# 1-Schematic_Line_Following.net
KiCad netlist of a schematic drawn in EasyEDA
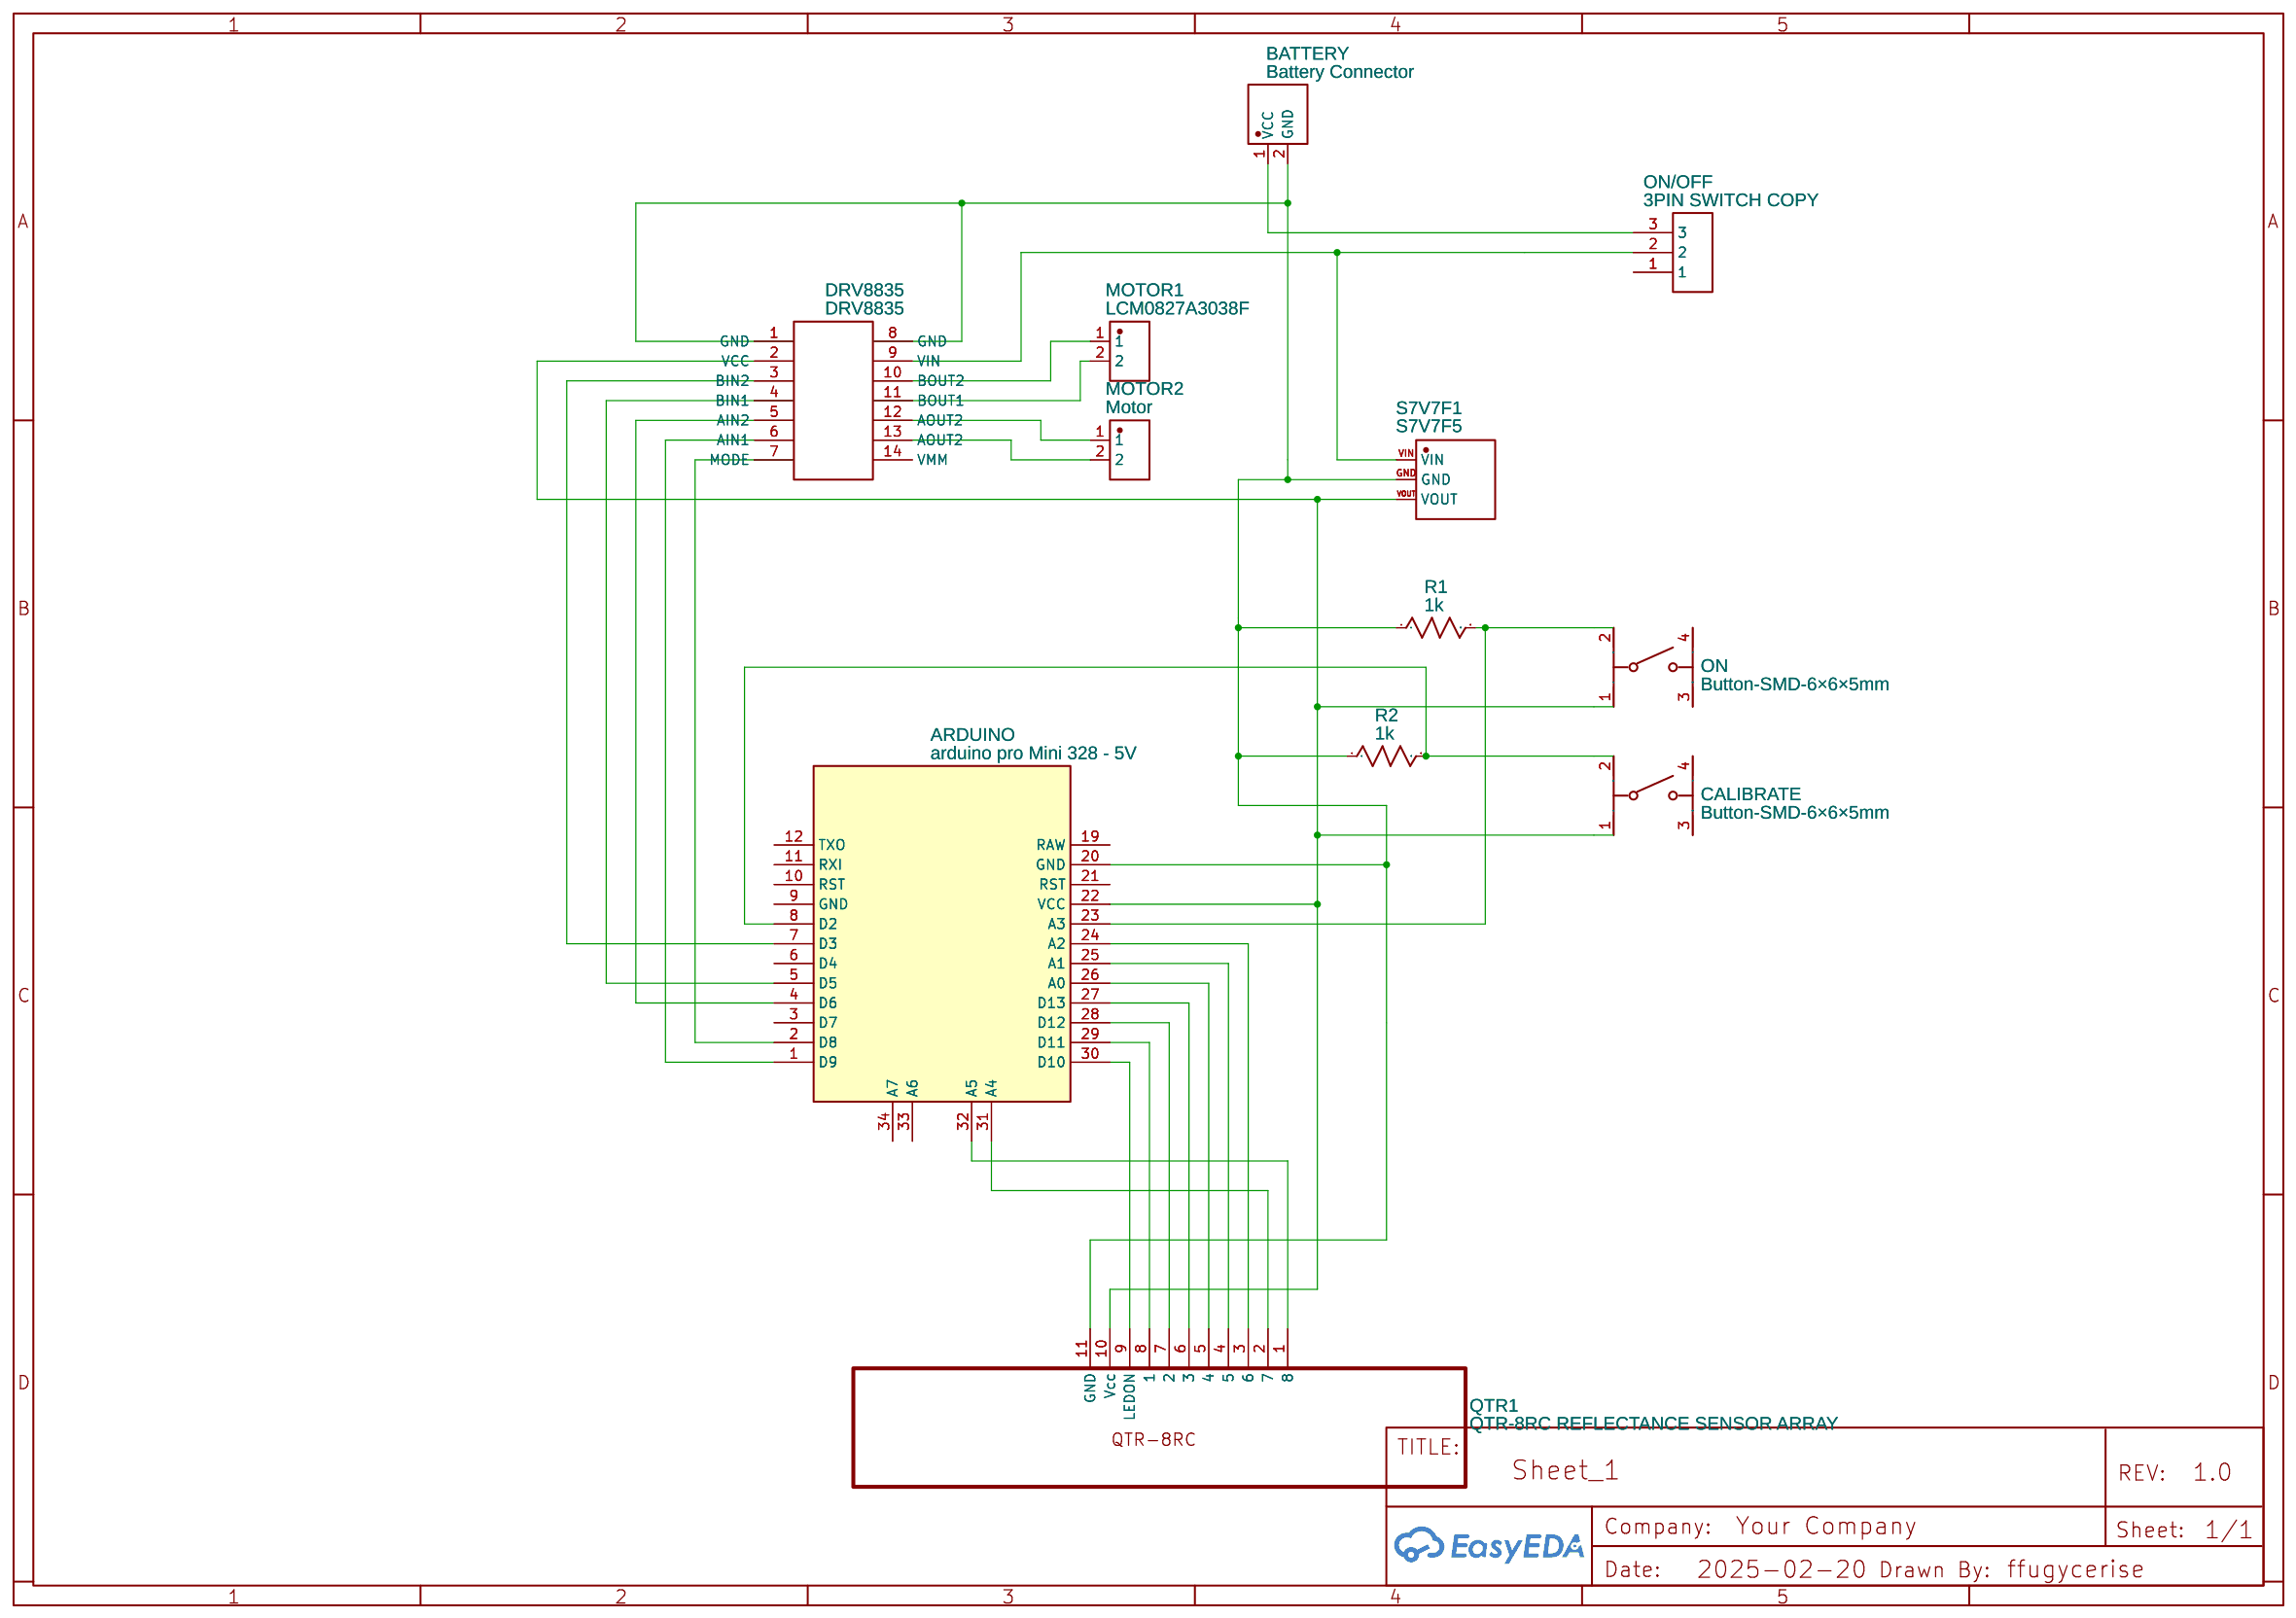
[diagram p0: schematic sheet]

(export (version "E")
  (design (tool "Eeschema 10.0.6"))
  (components
    (comp (ref "ARDUINO")
      (value "arduino pro Mini 328 - 5V")
      (libsource (lib "") (part "arduino pro Mini 328 - 5V"))
    )
    (comp (ref "BATTERY") (value "Battery Connector") (libsource (lib "") (part "Battery Connector")))
    (comp (ref "CALIBRATE")
      (value "Button-SMD-6×6×5mm")
      (fields (field (name "Manufacturer Part") "6×6×5mm 环保（嘉立创）"))
      (libsource (lib "") (part "Button-SMD-6×6×5mm_1"))
    )
    (comp (ref "DRV8835")
      (value "DRV8835")
      (fields (field (name "Manufacturer") "Pololu"))
      (libsource (lib "") (part "DRV8835"))
    )
    (comp (ref "MOTOR1")
      (value "LCM0827A3038F")
      (fields (field (name "Manufacturer") "LEADER(立得)"))
      (libsource (lib "") (part "LCM0827A3038F"))
    )
    (comp (ref "MOTOR2")
      (value "Motor")
      (fields (field (name "Manufacturer Part") "LCM0827A3038F") (field (name "Manufacturer") "LEADER(立得)"))
      (libsource (lib "") (part "LCM0827A3038F"))
    )
    (comp (ref "ON")
      (value "Button-SMD-6×6×5mm")
      (fields (field (name "Manufacturer Part") "6×6×5mm 环保（嘉立创）"))
      (libsource (lib "") (part "Button-SMD-6×6×5mm"))
    )
    (comp (ref "ON/OFF")
      (value "3PIN SWITCH COPY")
      (fields
        (field (name "Manufacturer Part") "SS12D06")
        (field (name "Manufacturer") "Dongguan Kaifeng Electronic Technology Limited")
      )
      (libsource (lib "") (part "3PIN SWITCH COPY"))
    )
    (comp (ref "QTR1")
      (value "QTR-8RC REFLECTANCE SENSOR ARRAY")
      (fields (field (name "Manufacturer Part") "961") (field (name "Manufacturer") "Pololu"))
      (libsource (lib "") (part "QTR-8RC REFLECTANCE SENSOR ARRAY"))
    )
    (comp (ref "R1") (value "1k") (libsource (lib "") (part "R_0603_US")))
    (comp (ref "R2") (value "1k") (libsource (lib "") (part "R_0603_US")))
    (comp (ref "S7V7F1") (value "S7V7F5") (libsource (lib "") (part "S7V7F5")))
  )
  (nets
    (net (code "1") (name "Net-(ARDUINO-A0)") (class "Default")
      (node (ref "ARDUINO") (pin "26") (pinfunction "A0_26") (pintype "unspecified"))
      (node (ref "QTR1") (pin "5") (pinfunction "4_5") (pintype "unspecified"))
    )
    (net (code "2") (name "Net-(ARDUINO-A1)") (class "Default")
      (node (ref "ARDUINO") (pin "25") (pinfunction "A1_25") (pintype "unspecified"))
      (node (ref "QTR1") (pin "4") (pinfunction "5_4") (pintype "unspecified"))
    )
    (net (code "3") (name "Net-(ARDUINO-A2)") (class "Default")
      (node (ref "ARDUINO") (pin "24") (pinfunction "A2_24") (pintype "unspecified"))
      (node (ref "QTR1") (pin "3") (pinfunction "6_3") (pintype "unspecified"))
    )
    (net (code "4") (name "Net-(ARDUINO-A3)") (class "Default")
      (node (ref "ARDUINO") (pin "23") (pinfunction "A3_23") (pintype "unspecified"))
      (node (ref "ON") (pin "2") (pinfunction "2_2") (pintype "unspecified"))
      (node (ref "R1") (pin "2") (pinfunction "2_2") (pintype "unspecified"))
    )
    (net (code "5") (name "Net-(ARDUINO-A4)") (class "Default")
      (node (ref "ARDUINO") (pin "31") (pinfunction "A4_31") (pintype "unspecified"))
      (node (ref "QTR1") (pin "2") (pinfunction "7_2") (pintype "unspecified"))
    )
    (net (code "6") (name "Net-(ARDUINO-A5)") (class "Default")
      (node (ref "ARDUINO") (pin "32") (pinfunction "A5_32") (pintype "unspecified"))
      (node (ref "QTR1") (pin "1") (pinfunction "8_1") (pintype "unspecified"))
    )
    (net (code "7") (name "Net-(ARDUINO-D2)") (class "Default")
      (node (ref "ARDUINO") (pin "8") (pinfunction "D2_8") (pintype "unspecified"))
      (node (ref "CALIBRATE") (pin "2") (pinfunction "2_2") (pintype "unspecified"))
      (node (ref "R2") (pin "2") (pinfunction "2_2") (pintype "unspecified"))
    )
    (net (code "8") (name "Net-(ARDUINO-D3)") (class "Default")
      (node (ref "ARDUINO") (pin "7") (pinfunction "D3_7") (pintype "unspecified"))
      (node (ref "DRV8835") (pin "3") (pinfunction "BIN2_3") (pintype "unspecified"))
    )
    (net (code "9") (name "Net-(ARDUINO-D5)") (class "Default")
      (node (ref "ARDUINO") (pin "5") (pinfunction "D5_5") (pintype "unspecified"))
      (node (ref "DRV8835") (pin "4") (pinfunction "BIN1_4") (pintype "unspecified"))
    )
    (net (code "10") (name "Net-(ARDUINO-D6)") (class "Default")
      (node (ref "ARDUINO") (pin "4") (pinfunction "D6_4") (pintype "unspecified"))
      (node (ref "DRV8835") (pin "5") (pinfunction "AIN2_5") (pintype "unspecified"))
    )
    (net (code "11") (name "Net-(ARDUINO-D8)") (class "Default")
      (node (ref "ARDUINO") (pin "2") (pinfunction "D8_2") (pintype "unspecified"))
      (node (ref "DRV8835") (pin "7") (pinfunction "MODE_7") (pintype "unspecified"))
    )
    (net (code "12") (name "Net-(ARDUINO-D9)") (class "Default")
      (node (ref "ARDUINO") (pin "1") (pinfunction "D9_1") (pintype "unspecified"))
      (node (ref "DRV8835") (pin "6") (pinfunction "AIN1_6") (pintype "unspecified"))
    )
    (net (code "13") (name "Net-(ARDUINO-D10)") (class "Default")
      (node (ref "ARDUINO") (pin "30") (pinfunction "D10_30") (pintype "unspecified"))
      (node (ref "QTR1") (pin "9") (pinfunction "LEDON_9") (pintype "unspecified"))
    )
    (net (code "14") (name "Net-(ARDUINO-D11)") (class "Default")
      (node (ref "ARDUINO") (pin "29") (pinfunction "D11_29") (pintype "unspecified"))
      (node (ref "QTR1") (pin "8") (pinfunction "1_8") (pintype "unspecified"))
    )
    (net (code "15") (name "Net-(ARDUINO-D12)") (class "Default")
      (node (ref "ARDUINO") (pin "28") (pinfunction "D12_28") (pintype "unspecified"))
      (node (ref "QTR1") (pin "7") (pinfunction "2_7") (pintype "unspecified"))
    )
    (net (code "16") (name "Net-(ARDUINO-D13)") (class "Default")
      (node (ref "ARDUINO") (pin "27") (pinfunction "D13_27") (pintype "unspecified"))
      (node (ref "QTR1") (pin "6") (pinfunction "3_6") (pintype "unspecified"))
    )
    (net (code "17") (name "Net-(ARDUINO-VCC)") (class "Default")
      (node (ref "ARDUINO") (pin "22") (pinfunction "VCC_22") (pintype "unspecified"))
      (node (ref "CALIBRATE") (pin "1") (pinfunction "1_1") (pintype "unspecified"))
      (node (ref "DRV8835") (pin "2") (pinfunction "VCC_2") (pintype "unspecified"))
      (node (ref "ON") (pin "1") (pinfunction "1_1") (pintype "unspecified"))
      (node (ref "QTR1") (pin "10") (pinfunction "Vcc_10") (pintype "unspecified"))
      (node (ref "S7V7F1") (pin "VOUT") (pinfunction "VOUT_VOUT") (pintype "unspecified"))
    )
    (net (code "18") (name "Net-(BATTERY-GND)") (class "Default")
      (node (ref "ARDUINO") (pin "20") (pinfunction "GND_20") (pintype "unspecified"))
      (node (ref "BATTERY") (pin "2") (pinfunction "GND_2") (pintype "unspecified"))
      (node (ref "DRV8835") (pin "1") (pinfunction "GND_1") (pintype "unspecified"))
      (node (ref "DRV8835") (pin "8") (pinfunction "GND_8") (pintype "unspecified"))
      (node (ref "QTR1") (pin "11") (pinfunction "GND_11") (pintype "unspecified"))
      (node (ref "R1") (pin "1") (pinfunction "1_1") (pintype "unspecified"))
      (node (ref "R2") (pin "1") (pinfunction "1_1") (pintype "unspecified"))
      (node (ref "S7V7F1") (pin "GND") (pinfunction "GND_GND") (pintype "unspecified"))
    )
    (net (code "19") (name "Net-(BATTERY-VCC)") (class "Default")
      (node (ref "BATTERY") (pin "1") (pinfunction "VCC_1") (pintype "unspecified"))
      (node (ref "ON/OFF") (pin "3") (pinfunction "3_3") (pintype "unspecified"))
    )
    (net (code "20") (name "Net-(DRV8835-AOUT2-Pad12)") (class "Default")
      (node (ref "DRV8835") (pin "12") (pinfunction "AOUT2_12") (pintype "unspecified"))
      (node (ref "MOTOR2") (pin "1") (pinfunction "1_1") (pintype "unspecified"))
    )
    (net (code "21") (name "Net-(DRV8835-AOUT2-Pad13)") (class "Default")
      (node (ref "DRV8835") (pin "13") (pinfunction "AOUT2_13") (pintype "unspecified"))
      (node (ref "MOTOR2") (pin "2") (pinfunction "2_2") (pintype "unspecified"))
    )
    (net (code "22") (name "Net-(DRV8835-BOUT1)") (class "Default")
      (node (ref "DRV8835") (pin "11") (pinfunction "BOUT1_11") (pintype "unspecified"))
      (node (ref "MOTOR1") (pin "2") (pinfunction "2_2") (pintype "unspecified"))
    )
    (net (code "23") (name "Net-(DRV8835-BOUT2)") (class "Default")
      (node (ref "DRV8835") (pin "10") (pinfunction "BOUT2_10") (pintype "unspecified"))
      (node (ref "MOTOR1") (pin "1") (pinfunction "1_1") (pintype "unspecified"))
    )
    (net (code "24") (name "Net-(DRV8835-VIN)") (class "Default")
      (node (ref "DRV8835") (pin "9") (pinfunction "VIN_9") (pintype "unspecified"))
      (node (ref "ON/OFF") (pin "2") (pinfunction "2_2") (pintype "unspecified"))
      (node (ref "S7V7F1") (pin "VIN") (pinfunction "VIN_VIN") (pintype "unspecified"))
    )
    (net (code "25") (name "unconnected-(ARDUINO-A6-Pad33)") (class "Default")
      (node (ref "ARDUINO") (pin "33") (pinfunction "A6_33") (pintype "unspecified"))
    )
    (net (code "26") (name "unconnected-(ARDUINO-A7-Pad34)") (class "Default")
      (node (ref "ARDUINO") (pin "34") (pinfunction "A7_34") (pintype "unspecified"))
    )
    (net (code "27") (name "unconnected-(ARDUINO-D4-Pad6)") (class "Default")
      (node (ref "ARDUINO") (pin "6") (pinfunction "D4_6") (pintype "unspecified"))
    )
    (net (code "28") (name "unconnected-(ARDUINO-D7-Pad3)") (class "Default")
      (node (ref "ARDUINO") (pin "3") (pinfunction "D7_3") (pintype "unspecified"))
    )
    (net (code "29") (name "unconnected-(ARDUINO-GND-Pad9)") (class "Default")
      (node (ref "ARDUINO") (pin "9") (pinfunction "GND_9") (pintype "unspecified"))
    )
    (net (code "30") (name "unconnected-(ARDUINO-RAW-Pad19)") (class "Default")
      (node (ref "ARDUINO") (pin "19") (pinfunction "RAW_19") (pintype "unspecified"))
    )
    (net (code "31") (name "unconnected-(ARDUINO-RST-Pad10)") (class "Default")
      (node (ref "ARDUINO") (pin "10") (pinfunction "RST_10") (pintype "unspecified"))
    )
    (net (code "32") (name "unconnected-(ARDUINO-RST-Pad21)") (class "Default")
      (node (ref "ARDUINO") (pin "21") (pinfunction "RST_21") (pintype "unspecified"))
    )
    (net (code "33") (name "unconnected-(ARDUINO-RXI-Pad11)") (class "Default")
      (node (ref "ARDUINO") (pin "11") (pinfunction "RXI_11") (pintype "unspecified"))
    )
    (net (code "34") (name "unconnected-(ARDUINO-TXO-Pad12)") (class "Default")
      (node (ref "ARDUINO") (pin "12") (pinfunction "TXO_12") (pintype "unspecified"))
    )
    (net (code "35") (name "unconnected-(CALIBRATE-Pad3)") (class "Default")
      (node (ref "CALIBRATE") (pin "3") (pinfunction "3_3") (pintype "unspecified"))
    )
    (net (code "36") (name "unconnected-(CALIBRATE-Pad4)") (class "Default")
      (node (ref "CALIBRATE") (pin "4") (pinfunction "4_4") (pintype "unspecified"))
    )
    (net (code "37") (name "unconnected-(DRV8835-VMM-Pad14)") (class "Default")
      (node (ref "DRV8835") (pin "14") (pinfunction "VMM_14") (pintype "unspecified"))
    )
    (net (code "38") (name "unconnected-(ON-Pad3)") (class "Default")
      (node (ref "ON") (pin "3") (pinfunction "3_3") (pintype "unspecified"))
    )
    (net (code "39") (name "unconnected-(ON-Pad4)") (class "Default")
      (node (ref "ON") (pin "4") (pinfunction "4_4") (pintype "unspecified"))
    )
    (net (code "40") (name "unconnected-(ON/OFF-Pad1)") (class "Default")
      (node (ref "ON/OFF") (pin "1") (pinfunction "1_1") (pintype "unspecified"))
    )
  )
)
